# PoERegulator8023af.net
KiCad netlist of a schematic drawn in EAGLE
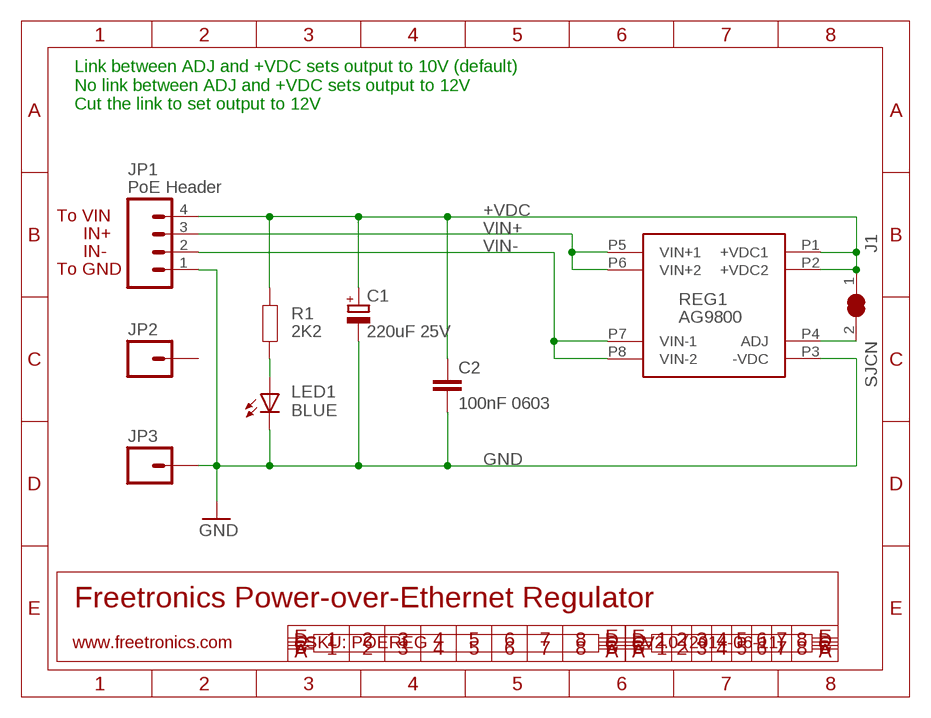
[diagram p0: schematic, sheet 1]

(export (version "E")
  (design (tool "Eeschema 10.0.6"))
  (components
    (comp (ref "C1")
      (value "220uF 25V")
      (footprint "eagle-import:PANASONIC_D")
      (libsource (lib "eagle-import") (part "CPOL-EUD"))
    )
    (comp (ref "C2")
      (value "100nF 0603")
      (footprint "eagle-import:0603")
      (libsource (lib "eagle-import") (part "CAP0603"))
    )
    (comp (ref "J1")
      (value "SJCN")
      (footprint "eagle-import:SJC")
      (libsource (lib "eagle-import") (part "SJCN"))
    )
    (comp (ref "JP1")
      (value "PoE Header")
      (footprint "eagle-import:1X04")
      (libsource (lib "eagle-import") (part "M04PTH"))
    )
    (comp (ref "JP2")
      (value "M01PTH")
      (footprint "eagle-import:1X01")
      (libsource (lib "eagle-import") (part "M01PTH"))
    )
    (comp (ref "JP3")
      (value "M01PTH")
      (footprint "eagle-import:1X01")
      (libsource (lib "eagle-import") (part "M01PTH"))
    )
    (comp (ref "LED1")
      (value "BLUE")
      (footprint "eagle-import:LED-0603")
      (libsource (lib "eagle-import") (part "LED0603"))
    )
    (comp (ref "R1")
      (value "2K2")
      (footprint "eagle-import:0603")
      (libsource (lib "eagle-import") (part "RESISTOR0603"))
    )
    (comp (ref "REG1")
      (value "AG9800")
      (footprint "eagle-import:AG9800")
      (libsource (lib "eagle-import") (part "AG9800"))
    )
  )
  (nets
    (net (code "1") (name "/+VDC") (class "Default")
      (node (ref "C1") (pin "+") (pinfunction "+_+") (pintype "passive"))
      (node (ref "C2") (pin "1") (pinfunction "1_1") (pintype "passive"))
      (node (ref "J1") (pin "1") (pinfunction "1_1") (pintype "passive"))
      (node (ref "JP1") (pin "4") (pinfunction "4_4") (pintype "passive"))
      (node (ref "R1") (pin "1") (pinfunction "1_1") (pintype "passive"))
      (node (ref "REG1") (pin "P1") (pinfunction "+VDC1_P1") (pintype "bidirectional"))
      (node (ref "REG1") (pin "P2") (pinfunction "+VDC2_P2") (pintype "bidirectional"))
    )
    (net (code "2") (name "/VIN+") (class "Default")
      (node (ref "JP1") (pin "3") (pinfunction "3_3") (pintype "passive"))
      (node (ref "REG1") (pin "P5") (pinfunction "VIN+1_P5") (pintype "power_in"))
      (node (ref "REG1") (pin "P6") (pinfunction "VIN+2_P6") (pintype "power_in"))
    )
    (net (code "3") (name "/VIN-") (class "Default")
      (node (ref "JP1") (pin "2") (pinfunction "2_2") (pintype "passive"))
      (node (ref "REG1") (pin "P7") (pinfunction "VIN-1_P7") (pintype "power_in"))
      (node (ref "REG1") (pin "P8") (pinfunction "VIN-2_P8") (pintype "power_in"))
    )
    (net (code "4") (name "GND") (class "Default")
      (node (ref "C1") (pin "-") (pinfunction "-_-") (pintype "passive"))
      (node (ref "C2") (pin "2") (pinfunction "2_2") (pintype "passive"))
      (node (ref "JP1") (pin "1") (pinfunction "1_1") (pintype "passive"))
      (node (ref "JP3") (pin "1") (pinfunction "1_1") (pintype "passive"))
      (node (ref "LED1") (pin "C") (pinfunction "C_C") (pintype "passive"))
      (node (ref "REG1") (pin "P3") (pinfunction "-VDC_P3") (pintype "bidirectional"))
    )
    (net (code "5") (name "Net-(LED1-PadA)") (class "Default")
      (node (ref "LED1") (pin "A") (pinfunction "A_A") (pintype "passive"))
      (node (ref "R1") (pin "2") (pinfunction "2_2") (pintype "passive"))
    )
    (net (code "6") (name "Net-(REG1-ADJ)") (class "Default")
      (node (ref "J1") (pin "2") (pinfunction "2_2") (pintype "passive"))
      (node (ref "REG1") (pin "P4") (pinfunction "ADJ_P4") (pintype "input"))
    )
    (net (code "7") (name "unconnected-(JP2-Pad1)") (class "Default")
      (node (ref "JP2") (pin "1") (pinfunction "1_1") (pintype "passive"))
    )
  )
)
